# Power_Entry_24v-3pin_Fused-1A5.net
KiCad netlist of a schematic drawn in Altium Designer
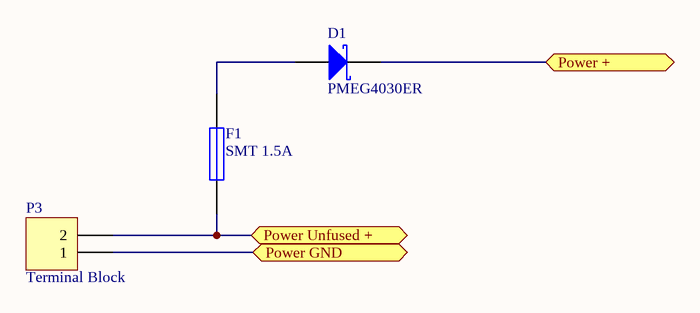
[diagram p0: Power Entry 24v-3pin Fused-1A5.SchDoc]

(export (version "E")
  (design (tool "Eeschema 10.0.6"))
  (components
    (comp (ref "D1")
      (value "PMEG4030ER")
      (footprint "SOD123W")
      (fields (field (name "VOLTAGE") "40V") (field (name "AUTHOR") "Willem Pietersz"))
      (libsource (lib "OurDb") (part "SCHOTTKY"))
    )
    (comp (ref "F1")
      (value "SMT 1.5A")
      (footprint "F_2920L185")
      (description "Fuse")
      (fields
        (field (name "PART NUMBER") "2920L185")
        (field (name "VOLTAGE") "30V")
        (field (name "PUBLISHER") "Altium Limited")
      )
      (libsource (lib "OurDb") (part "Fuse 1"))
    )
    (comp (ref "P3")
      (value "Terminal Block")
      (footprint "TB2_3.5")
      (description "Con1x2")
      (fields
        (field (name "PART NUMBER") "TB2")
        (field (name "VOLTAGE") "300")
        (field (name "AUTHOR") "Willy Pietersz")
      )
      (libsource (lib "OurDb") (part "Con1x2"))
    )
  )
  (nets
    (net (code "1") (name "/Power +") (class "Default")
      (node (ref "D1") (pin "2") (pinfunction "2_2") (pintype "passive"))
    )
    (net (code "2") (name "/Power GND") (class "Default")
      (node (ref "P3") (pin "1") (pinfunction "1_1") (pintype "passive"))
    )
    (net (code "3") (name "/Power Unfused +") (class "Default")
      (node (ref "F1") (pin "1") (pinfunction "1_1") (pintype "passive"))
      (node (ref "P3") (pin "2") (pinfunction "2_2") (pintype "passive"))
    )
    (net (code "4") (name "Net-(D1-Pad1)") (class "Default")
      (node (ref "D1") (pin "1") (pinfunction "1_1") (pintype "passive"))
      (node (ref "F1") (pin "2") (pinfunction "2_2") (pintype "passive"))
    )
  )
)
